# BPMLabLineSensor.net
KiCad netlist of a schematic drawn in EAGLE
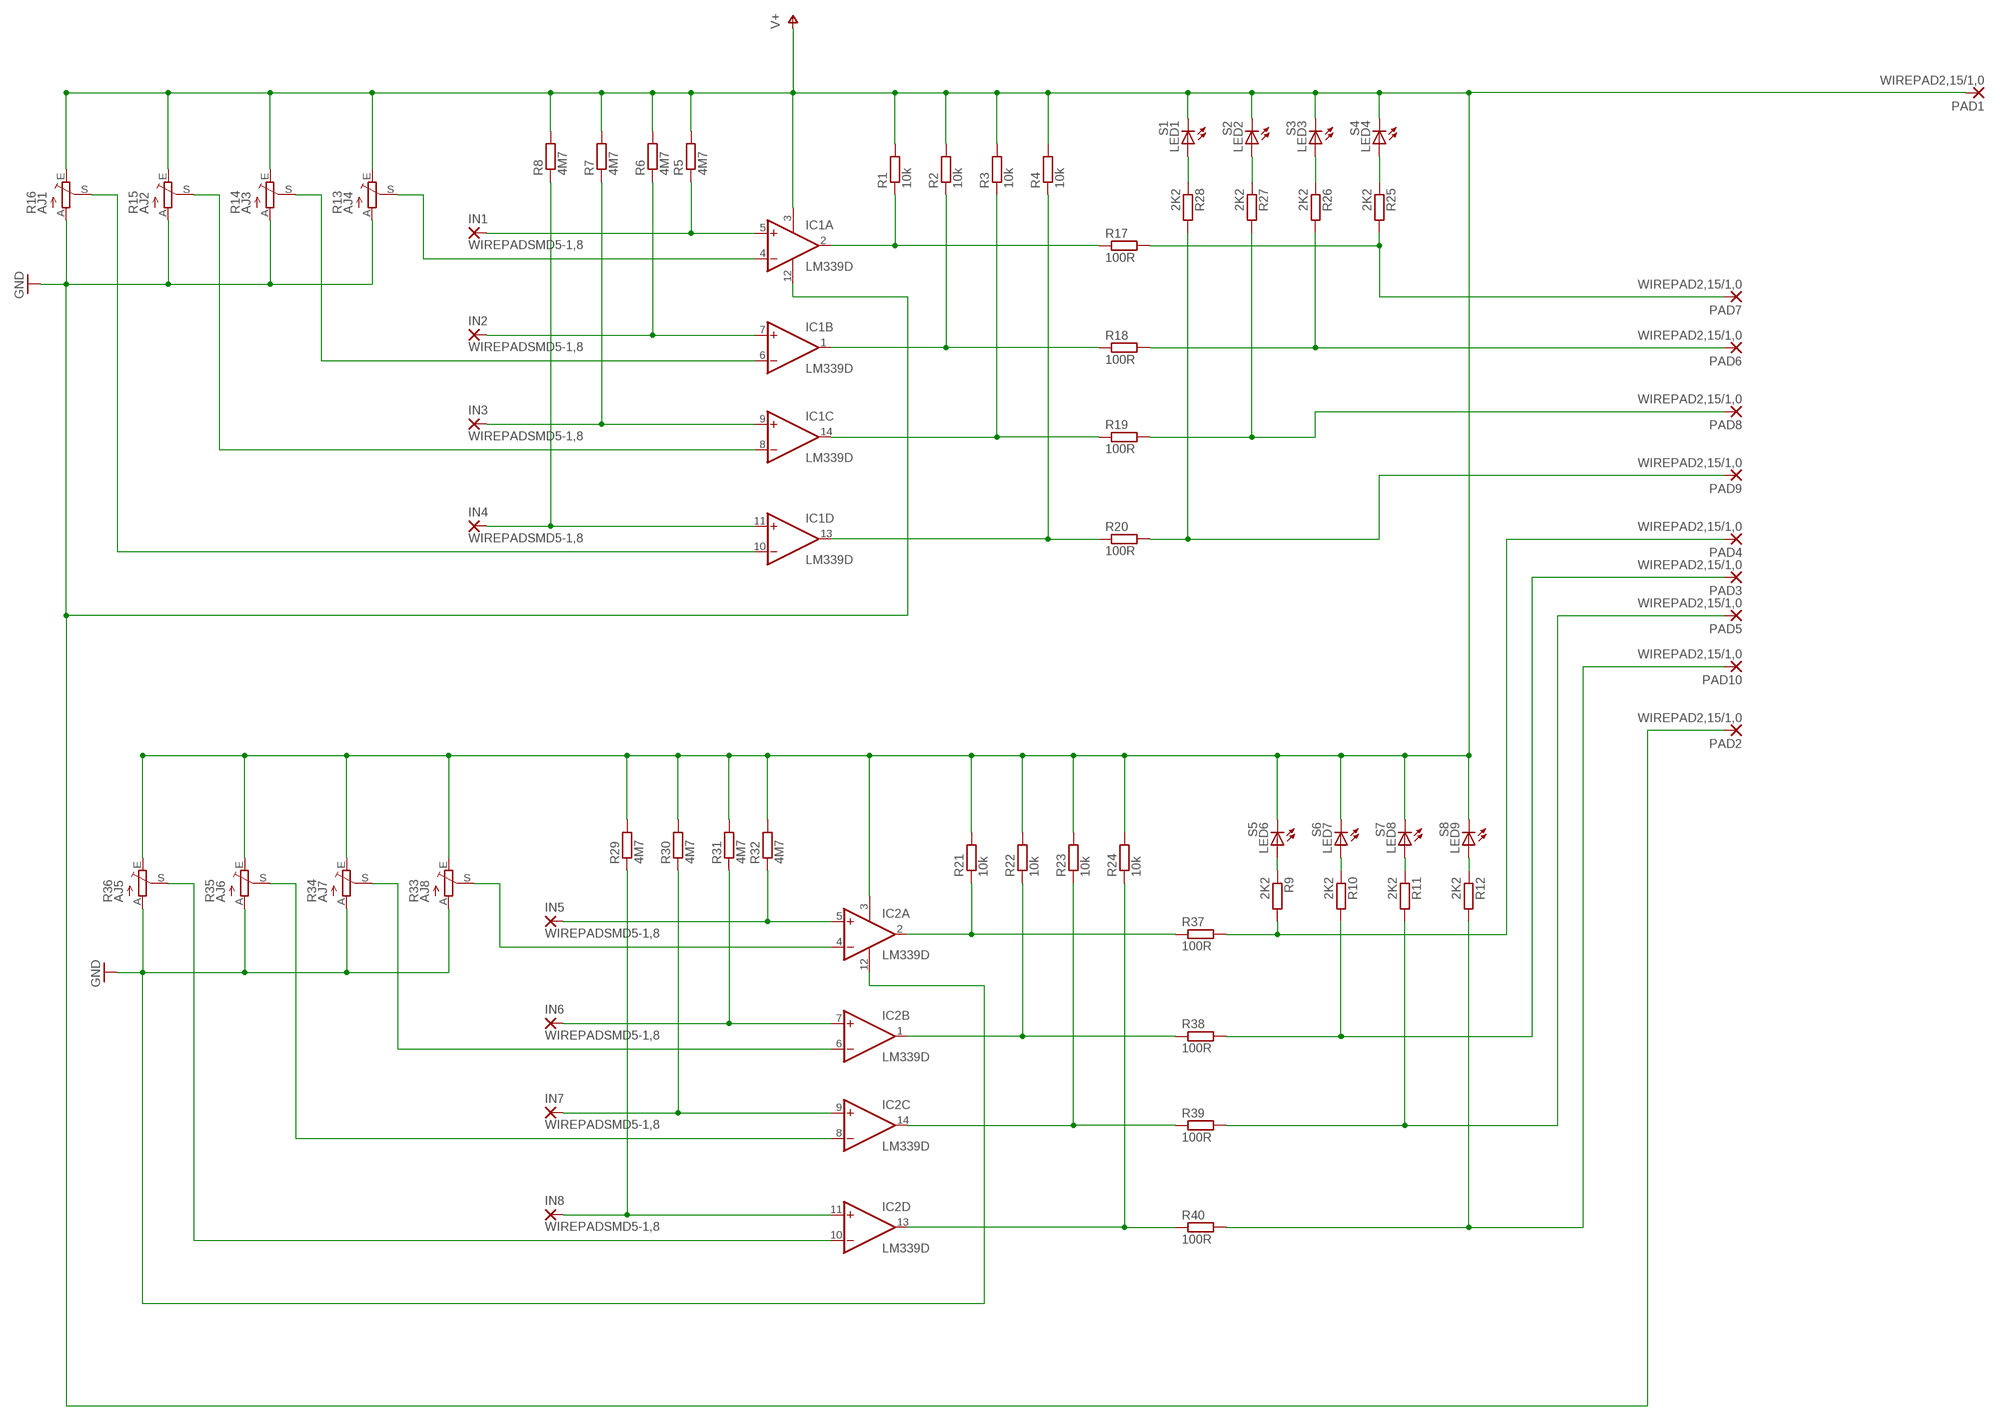
[diagram p0: schematic, sheet 1]

(export (version "E")
  (design (tool "Eeschema 10.0.6"))
  (components
    (comp (ref "IC1")
      (value "LM339D")
      (footprint "eagle-import:SO14")
      (libsource (lib "eagle-import") (part "LM339D"))
    )
    (comp (ref "IC2")
      (value "LM339D")
      (footprint "eagle-import:SO14")
      (libsource (lib "eagle-import") (part "LM339D"))
    )
    (comp (ref "IN1")
      (value "WIREPADSMD5-1,8")
      (footprint "eagle-import:5-1,8")
      (libsource (lib "eagle-import") (part "WIREPADSMD5-1,8"))
    )
    (comp (ref "IN2")
      (value "WIREPADSMD5-1,8")
      (footprint "eagle-import:5-1,8")
      (libsource (lib "eagle-import") (part "WIREPADSMD5-1,8"))
    )
    (comp (ref "IN3")
      (value "WIREPADSMD5-1,8")
      (footprint "eagle-import:5-1,8")
      (libsource (lib "eagle-import") (part "WIREPADSMD5-1,8"))
    )
    (comp (ref "IN4")
      (value "WIREPADSMD5-1,8")
      (footprint "eagle-import:5-1,8")
      (libsource (lib "eagle-import") (part "WIREPADSMD5-1,8"))
    )
    (comp (ref "IN5")
      (value "WIREPADSMD5-1,8")
      (footprint "eagle-import:5-1,8")
      (libsource (lib "eagle-import") (part "WIREPADSMD5-1,8"))
    )
    (comp (ref "IN6")
      (value "WIREPADSMD5-1,8")
      (footprint "eagle-import:5-1,8")
      (libsource (lib "eagle-import") (part "WIREPADSMD5-1,8"))
    )
    (comp (ref "IN7")
      (value "WIREPADSMD5-1,8")
      (footprint "eagle-import:5-1,8")
      (libsource (lib "eagle-import") (part "WIREPADSMD5-1,8"))
    )
    (comp (ref "IN8")
      (value "WIREPADSMD5-1,8")
      (footprint "eagle-import:5-1,8")
      (libsource (lib "eagle-import") (part "WIREPADSMD5-1,8"))
    )
    (comp (ref "LED1")
      (value "S1")
      (footprint "eagle-import:LED5MM")
      (libsource (lib "eagle-import") (part "LED5MM"))
    )
    (comp (ref "LED2")
      (value "S2")
      (footprint "eagle-import:LED5MM")
      (libsource (lib "eagle-import") (part "LED5MM"))
    )
    (comp (ref "LED3")
      (value "S3")
      (footprint "eagle-import:LED5MM")
      (libsource (lib "eagle-import") (part "LED5MM"))
    )
    (comp (ref "LED4")
      (value "S4")
      (footprint "eagle-import:LED5MM")
      (libsource (lib "eagle-import") (part "LED5MM"))
    )
    (comp (ref "LED6")
      (value "S5")
      (footprint "eagle-import:LED5MM")
      (libsource (lib "eagle-import") (part "LED5MM"))
    )
    (comp (ref "LED7")
      (value "S6")
      (footprint "eagle-import:LED5MM")
      (libsource (lib "eagle-import") (part "LED5MM"))
    )
    (comp (ref "LED8")
      (value "S7")
      (footprint "eagle-import:LED5MM")
      (libsource (lib "eagle-import") (part "LED5MM"))
    )
    (comp (ref "LED9")
      (value "S8")
      (footprint "eagle-import:LED5MM")
      (libsource (lib "eagle-import") (part "LED5MM"))
    )
    (comp (ref "PAD1")
      (value "WIREPAD2,15/1,0")
      (footprint "eagle-import:2,15_1,0")
      (libsource (lib "eagle-import") (part "WIREPAD2,15/1,0"))
    )
    (comp (ref "PAD2")
      (value "WIREPAD2,15/1,0")
      (footprint "eagle-import:2,15_1,0")
      (libsource (lib "eagle-import") (part "WIREPAD2,15/1,0"))
    )
    (comp (ref "PAD3")
      (value "WIREPAD2,15/1,0")
      (footprint "eagle-import:2,15_1,0")
      (libsource (lib "eagle-import") (part "WIREPAD2,15/1,0"))
    )
    (comp (ref "PAD4")
      (value "WIREPAD2,15/1,0")
      (footprint "eagle-import:2,15_1,0")
      (libsource (lib "eagle-import") (part "WIREPAD2,15/1,0"))
    )
    (comp (ref "PAD5")
      (value "WIREPAD2,15/1,0")
      (footprint "eagle-import:2,15_1,0")
      (libsource (lib "eagle-import") (part "WIREPAD2,15/1,0"))
    )
    (comp (ref "PAD6")
      (value "WIREPAD2,15/1,0")
      (footprint "eagle-import:2,15_1,0")
      (libsource (lib "eagle-import") (part "WIREPAD2,15/1,0"))
    )
    (comp (ref "PAD7")
      (value "WIREPAD2,15/1,0")
      (footprint "eagle-import:2,15_1,0")
      (libsource (lib "eagle-import") (part "WIREPAD2,15/1,0"))
    )
    (comp (ref "PAD8")
      (value "WIREPAD2,15/1,0")
      (footprint "eagle-import:2,15_1,0")
      (libsource (lib "eagle-import") (part "WIREPAD2,15/1,0"))
    )
    (comp (ref "PAD9")
      (value "WIREPAD2,15/1,0")
      (footprint "eagle-import:2,15_1,0")
      (libsource (lib "eagle-import") (part "WIREPAD2,15/1,0"))
    )
    (comp (ref "PAD10")
      (value "WIREPAD2,15/1,0")
      (footprint "eagle-import:2,15_1,0")
      (libsource (lib "eagle-import") (part "WIREPAD2,15/1,0"))
    )
    (comp (ref "R1")
      (value "10k")
      (footprint "eagle-import:M0805")
      (libsource (lib "eagle-import") (part "R-EU_M0805"))
    )
    (comp (ref "R2")
      (value "10k")
      (footprint "eagle-import:M0805")
      (libsource (lib "eagle-import") (part "R-EU_M0805"))
    )
    (comp (ref "R3")
      (value "10k")
      (footprint "eagle-import:M0805")
      (libsource (lib "eagle-import") (part "R-EU_M0805"))
    )
    (comp (ref "R4")
      (value "10k")
      (footprint "eagle-import:M0805")
      (libsource (lib "eagle-import") (part "R-EU_M0805"))
    )
    (comp (ref "R5")
      (value "4M7")
      (footprint "eagle-import:M0805")
      (libsource (lib "eagle-import") (part "R-EU_M0805"))
    )
    (comp (ref "R6")
      (value "4M7")
      (footprint "eagle-import:M0805")
      (libsource (lib "eagle-import") (part "R-EU_M0805"))
    )
    (comp (ref "R7")
      (value "4M7")
      (footprint "eagle-import:M0805")
      (libsource (lib "eagle-import") (part "R-EU_M0805"))
    )
    (comp (ref "R8")
      (value "4M7")
      (footprint "eagle-import:M0805")
      (libsource (lib "eagle-import") (part "R-EU_M0805"))
    )
    (comp (ref "R9")
      (value "2K2")
      (footprint "eagle-import:M0805")
      (libsource (lib "eagle-import") (part "R-EU_M0805"))
    )
    (comp (ref "R10")
      (value "2K2")
      (footprint "eagle-import:M0805")
      (libsource (lib "eagle-import") (part "R-EU_M0805"))
    )
    (comp (ref "R11")
      (value "2K2")
      (footprint "eagle-import:M0805")
      (libsource (lib "eagle-import") (part "R-EU_M0805"))
    )
    (comp (ref "R12")
      (value "2K2")
      (footprint "eagle-import:M0805")
      (libsource (lib "eagle-import") (part "R-EU_M0805"))
    )
    (comp (ref "R13")
      (value "AJ4")
      (footprint "eagle-import:RS3")
      (libsource (lib "eagle-import") (part "TRIM_EU-RS3"))
    )
    (comp (ref "R14")
      (value "AJ3")
      (footprint "eagle-import:RS3")
      (libsource (lib "eagle-import") (part "TRIM_EU-RS3"))
    )
    (comp (ref "R15")
      (value "AJ2")
      (footprint "eagle-import:RS3")
      (libsource (lib "eagle-import") (part "TRIM_EU-RS3"))
    )
    (comp (ref "R16")
      (value "AJ1")
      (footprint "eagle-import:RS3")
      (libsource (lib "eagle-import") (part "TRIM_EU-RS3"))
    )
    (comp (ref "R17")
      (value "100R")
      (footprint "eagle-import:0204_7")
      (libsource (lib "eagle-import") (part "R-EU_0204/7"))
    )
    (comp (ref "R18")
      (value "100R")
      (footprint "eagle-import:0204_7")
      (libsource (lib "eagle-import") (part "R-EU_0204/7"))
    )
    (comp (ref "R19")
      (value "100R")
      (footprint "eagle-import:0204_7")
      (libsource (lib "eagle-import") (part "R-EU_0204/7"))
    )
    (comp (ref "R20")
      (value "100R")
      (footprint "eagle-import:0204_7")
      (libsource (lib "eagle-import") (part "R-EU_0204/7"))
    )
    (comp (ref "R21")
      (value "10k")
      (footprint "eagle-import:M0805")
      (libsource (lib "eagle-import") (part "R-EU_M0805"))
    )
    (comp (ref "R22")
      (value "10k")
      (footprint "eagle-import:M0805")
      (libsource (lib "eagle-import") (part "R-EU_M0805"))
    )
    (comp (ref "R23")
      (value "10k")
      (footprint "eagle-import:M0805")
      (libsource (lib "eagle-import") (part "R-EU_M0805"))
    )
    (comp (ref "R24")
      (value "10k")
      (footprint "eagle-import:M0805")
      (libsource (lib "eagle-import") (part "R-EU_M0805"))
    )
    (comp (ref "R25")
      (value "2K2")
      (footprint "eagle-import:M0805")
      (libsource (lib "eagle-import") (part "R-EU_M0805"))
    )
    (comp (ref "R26")
      (value "2K2")
      (footprint "eagle-import:M0805")
      (libsource (lib "eagle-import") (part "R-EU_M0805"))
    )
    (comp (ref "R27")
      (value "2K2")
      (footprint "eagle-import:M0805")
      (libsource (lib "eagle-import") (part "R-EU_M0805"))
    )
    (comp (ref "R28")
      (value "2K2")
      (footprint "eagle-import:M0805")
      (libsource (lib "eagle-import") (part "R-EU_M0805"))
    )
    (comp (ref "R29")
      (value "4M7")
      (footprint "eagle-import:M0805")
      (libsource (lib "eagle-import") (part "R-EU_M0805"))
    )
    (comp (ref "R30")
      (value "4M7")
      (footprint "eagle-import:M0805")
      (libsource (lib "eagle-import") (part "R-EU_M0805"))
    )
    (comp (ref "R31")
      (value "4M7")
      (footprint "eagle-import:M0805")
      (libsource (lib "eagle-import") (part "R-EU_M0805"))
    )
    (comp (ref "R32")
      (value "4M7")
      (footprint "eagle-import:M0805")
      (libsource (lib "eagle-import") (part "R-EU_M0805"))
    )
    (comp (ref "R33")
      (value "AJ8")
      (footprint "eagle-import:RS3")
      (libsource (lib "eagle-import") (part "TRIM_EU-RS3"))
    )
    (comp (ref "R34")
      (value "AJ7")
      (footprint "eagle-import:RS3")
      (libsource (lib "eagle-import") (part "TRIM_EU-RS3"))
    )
    (comp (ref "R35")
      (value "AJ6")
      (footprint "eagle-import:RS3")
      (libsource (lib "eagle-import") (part "TRIM_EU-RS3"))
    )
    (comp (ref "R36")
      (value "AJ5")
      (footprint "eagle-import:RS3")
      (libsource (lib "eagle-import") (part "TRIM_EU-RS3"))
    )
    (comp (ref "R37")
      (value "100R")
      (footprint "eagle-import:0204_7")
      (libsource (lib "eagle-import") (part "R-EU_0204/7"))
    )
    (comp (ref "R38")
      (value "100R")
      (footprint "eagle-import:0204_7")
      (libsource (lib "eagle-import") (part "R-EU_0204/7"))
    )
    (comp (ref "R39")
      (value "100R")
      (footprint "eagle-import:0204_7")
      (libsource (lib "eagle-import") (part "R-EU_0204/7"))
    )
    (comp (ref "R40")
      (value "100R")
      (footprint "eagle-import:0204_7")
      (libsource (lib "eagle-import") (part "R-EU_0204/7"))
    )
  )
  (nets
    (net (code "1") (name "GND") (class "Default")
      (node (ref "IC1") (pin "12") (pinfunction "GND_12") (pintype "power_in"))
      (node (ref "IC2") (pin "12") (pinfunction "GND_12") (pintype "power_in"))
      (node (ref "PAD2") (pin "1") (pinfunction "P_1") (pintype "passive"))
      (node (ref "R13") (pin "A") (pinfunction "A_A") (pintype "passive"))
      (node (ref "R14") (pin "A") (pinfunction "A_A") (pintype "passive"))
      (node (ref "R15") (pin "A") (pinfunction "A_A") (pintype "passive"))
      (node (ref "R16") (pin "A") (pinfunction "A_A") (pintype "passive"))
      (node (ref "R33") (pin "A") (pinfunction "A_A") (pintype "passive"))
      (node (ref "R34") (pin "A") (pinfunction "A_A") (pintype "passive"))
      (node (ref "R35") (pin "A") (pinfunction "A_A") (pintype "passive"))
      (node (ref "R36") (pin "A") (pinfunction "A_A") (pintype "passive"))
    )
    (net (code "2") (name "Net-(IC1A-+IN)") (class "Default")
      (node (ref "IC1") (pin "5") (pinfunction "+IN_5") (pintype "input"))
      (node (ref "IN1") (pin "1") (pinfunction "P_1") (pintype "passive"))
      (node (ref "R5") (pin "1") (pinfunction "1_1") (pintype "passive"))
    )
    (net (code "3") (name "Net-(IC1A--IN)") (class "Default")
      (node (ref "IC1") (pin "4") (pinfunction "-IN_4") (pintype "input"))
      (node (ref "R13") (pin "S") (pinfunction "S_S") (pintype "passive"))
    )
    (net (code "4") (name "Net-(IC1A-OUT)") (class "Default")
      (node (ref "IC1") (pin "2") (pinfunction "OUT_2") (pintype "open_collector"))
      (node (ref "R1") (pin "1") (pinfunction "1_1") (pintype "passive"))
      (node (ref "R17") (pin "1") (pinfunction "1_1") (pintype "passive"))
    )
    (net (code "5") (name "Net-(IC1B-+IN)") (class "Default")
      (node (ref "IC1") (pin "7") (pinfunction "+IN_7") (pintype "input"))
      (node (ref "IN2") (pin "1") (pinfunction "P_1") (pintype "passive"))
      (node (ref "R6") (pin "1") (pinfunction "1_1") (pintype "passive"))
    )
    (net (code "6") (name "Net-(IC1B--IN)") (class "Default")
      (node (ref "IC1") (pin "6") (pinfunction "-IN_6") (pintype "input"))
      (node (ref "R14") (pin "S") (pinfunction "S_S") (pintype "passive"))
    )
    (net (code "7") (name "Net-(IC1B-OUT)") (class "Default")
      (node (ref "IC1") (pin "1") (pinfunction "OUT_1") (pintype "open_collector"))
      (node (ref "R18") (pin "1") (pinfunction "1_1") (pintype "passive"))
      (node (ref "R2") (pin "1") (pinfunction "1_1") (pintype "passive"))
    )
    (net (code "8") (name "Net-(IC1C-+IN)") (class "Default")
      (node (ref "IC1") (pin "9") (pinfunction "+IN_9") (pintype "input"))
      (node (ref "IN3") (pin "1") (pinfunction "P_1") (pintype "passive"))
      (node (ref "R7") (pin "1") (pinfunction "1_1") (pintype "passive"))
    )
    (net (code "9") (name "Net-(IC1C--IN)") (class "Default")
      (node (ref "IC1") (pin "8") (pinfunction "-IN_8") (pintype "input"))
      (node (ref "R15") (pin "S") (pinfunction "S_S") (pintype "passive"))
    )
    (net (code "10") (name "Net-(IC1C-OUT)") (class "Default")
      (node (ref "IC1") (pin "14") (pinfunction "OUT_14") (pintype "open_collector"))
      (node (ref "R19") (pin "1") (pinfunction "1_1") (pintype "passive"))
      (node (ref "R3") (pin "1") (pinfunction "1_1") (pintype "passive"))
    )
    (net (code "11") (name "Net-(IC1D-+IN)") (class "Default")
      (node (ref "IC1") (pin "11") (pinfunction "+IN_11") (pintype "input"))
      (node (ref "IN4") (pin "1") (pinfunction "P_1") (pintype "passive"))
      (node (ref "R8") (pin "1") (pinfunction "1_1") (pintype "passive"))
    )
    (net (code "12") (name "Net-(IC1D--IN)") (class "Default")
      (node (ref "IC1") (pin "10") (pinfunction "-IN_10") (pintype "input"))
      (node (ref "R16") (pin "S") (pinfunction "S_S") (pintype "passive"))
    )
    (net (code "13") (name "Net-(IC1D-OUT)") (class "Default")
      (node (ref "IC1") (pin "13") (pinfunction "OUT_13") (pintype "open_collector"))
      (node (ref "R20") (pin "1") (pinfunction "1_1") (pintype "passive"))
      (node (ref "R4") (pin "1") (pinfunction "1_1") (pintype "passive"))
    )
    (net (code "14") (name "Net-(IC2A-+IN)") (class "Default")
      (node (ref "IC2") (pin "5") (pinfunction "+IN_5") (pintype "input"))
      (node (ref "IN5") (pin "1") (pinfunction "P_1") (pintype "passive"))
      (node (ref "R32") (pin "1") (pinfunction "1_1") (pintype "passive"))
    )
    (net (code "15") (name "Net-(IC2A--IN)") (class "Default")
      (node (ref "IC2") (pin "4") (pinfunction "-IN_4") (pintype "input"))
      (node (ref "R33") (pin "S") (pinfunction "S_S") (pintype "passive"))
    )
    (net (code "16") (name "Net-(IC2A-OUT)") (class "Default")
      (node (ref "IC2") (pin "2") (pinfunction "OUT_2") (pintype "open_collector"))
      (node (ref "R21") (pin "1") (pinfunction "1_1") (pintype "passive"))
      (node (ref "R37") (pin "1") (pinfunction "1_1") (pintype "passive"))
    )
    (net (code "17") (name "Net-(IC2B-+IN)") (class "Default")
      (node (ref "IC2") (pin "7") (pinfunction "+IN_7") (pintype "input"))
      (node (ref "IN6") (pin "1") (pinfunction "P_1") (pintype "passive"))
      (node (ref "R31") (pin "1") (pinfunction "1_1") (pintype "passive"))
    )
    (net (code "18") (name "Net-(IC2B--IN)") (class "Default")
      (node (ref "IC2") (pin "6") (pinfunction "-IN_6") (pintype "input"))
      (node (ref "R34") (pin "S") (pinfunction "S_S") (pintype "passive"))
    )
    (net (code "19") (name "Net-(IC2B-OUT)") (class "Default")
      (node (ref "IC2") (pin "1") (pinfunction "OUT_1") (pintype "open_collector"))
      (node (ref "R22") (pin "1") (pinfunction "1_1") (pintype "passive"))
      (node (ref "R38") (pin "1") (pinfunction "1_1") (pintype "passive"))
    )
    (net (code "20") (name "Net-(IC2C-+IN)") (class "Default")
      (node (ref "IC2") (pin "9") (pinfunction "+IN_9") (pintype "input"))
      (node (ref "IN7") (pin "1") (pinfunction "P_1") (pintype "passive"))
      (node (ref "R30") (pin "1") (pinfunction "1_1") (pintype "passive"))
    )
    (net (code "21") (name "Net-(IC2C--IN)") (class "Default")
      (node (ref "IC2") (pin "8") (pinfunction "-IN_8") (pintype "input"))
      (node (ref "R35") (pin "S") (pinfunction "S_S") (pintype "passive"))
    )
    (net (code "22") (name "Net-(IC2C-OUT)") (class "Default")
      (node (ref "IC2") (pin "14") (pinfunction "OUT_14") (pintype "open_collector"))
      (node (ref "R23") (pin "1") (pinfunction "1_1") (pintype "passive"))
      (node (ref "R39") (pin "1") (pinfunction "1_1") (pintype "passive"))
    )
    (net (code "23") (name "Net-(IC2D-+IN)") (class "Default")
      (node (ref "IC2") (pin "11") (pinfunction "+IN_11") (pintype "input"))
      (node (ref "IN8") (pin "1") (pinfunction "P_1") (pintype "passive"))
      (node (ref "R29") (pin "1") (pinfunction "1_1") (pintype "passive"))
    )
    (net (code "24") (name "Net-(IC2D--IN)") (class "Default")
      (node (ref "IC2") (pin "10") (pinfunction "-IN_10") (pintype "input"))
      (node (ref "R36") (pin "S") (pinfunction "S_S") (pintype "passive"))
    )
    (net (code "25") (name "Net-(IC2D-OUT)") (class "Default")
      (node (ref "IC2") (pin "13") (pinfunction "OUT_13") (pintype "open_collector"))
      (node (ref "R24") (pin "1") (pinfunction "1_1") (pintype "passive"))
      (node (ref "R40") (pin "1") (pinfunction "1_1") (pintype "passive"))
    )
    (net (code "26") (name "Net-(LED1-PadA)") (class "Default")
      (node (ref "LED1") (pin "A") (pinfunction "A_A") (pintype "passive"))
      (node (ref "R28") (pin "1") (pinfunction "1_1") (pintype "passive"))
    )
    (net (code "27") (name "Net-(LED2-PadA)") (class "Default")
      (node (ref "LED2") (pin "A") (pinfunction "A_A") (pintype "passive"))
      (node (ref "R27") (pin "1") (pinfunction "1_1") (pintype "passive"))
    )
    (net (code "28") (name "Net-(LED3-PadA)") (class "Default")
      (node (ref "LED3") (pin "A") (pinfunction "A_A") (pintype "passive"))
      (node (ref "R26") (pin "1") (pinfunction "1_1") (pintype "passive"))
    )
    (net (code "29") (name "Net-(LED4-PadA)") (class "Default")
      (node (ref "LED4") (pin "A") (pinfunction "A_A") (pintype "passive"))
      (node (ref "R25") (pin "1") (pinfunction "1_1") (pintype "passive"))
    )
    (net (code "30") (name "Net-(LED6-PadA)") (class "Default")
      (node (ref "LED6") (pin "A") (pinfunction "A_A") (pintype "passive"))
      (node (ref "R9") (pin "1") (pinfunction "1_1") (pintype "passive"))
    )
    (net (code "31") (name "Net-(LED7-PadA)") (class "Default")
      (node (ref "LED7") (pin "A") (pinfunction "A_A") (pintype "passive"))
      (node (ref "R10") (pin "1") (pinfunction "1_1") (pintype "passive"))
    )
    (net (code "32") (name "Net-(LED8-PadA)") (class "Default")
      (node (ref "LED8") (pin "A") (pinfunction "A_A") (pintype "passive"))
      (node (ref "R11") (pin "1") (pinfunction "1_1") (pintype "passive"))
    )
    (net (code "33") (name "Net-(LED9-PadA)") (class "Default")
      (node (ref "LED9") (pin "A") (pinfunction "A_A") (pintype "passive"))
      (node (ref "R12") (pin "1") (pinfunction "1_1") (pintype "passive"))
    )
    (net (code "34") (name "Net-(PAD3-P)") (class "Default")
      (node (ref "PAD3") (pin "1") (pinfunction "P_1") (pintype "passive"))
      (node (ref "R10") (pin "2") (pinfunction "2_2") (pintype "passive"))
      (node (ref "R38") (pin "2") (pinfunction "2_2") (pintype "passive"))
    )
    (net (code "35") (name "Net-(PAD4-P)") (class "Default")
      (node (ref "PAD4") (pin "1") (pinfunction "P_1") (pintype "passive"))
      (node (ref "R37") (pin "2") (pinfunction "2_2") (pintype "passive"))
      (node (ref "R9") (pin "2") (pinfunction "2_2") (pintype "passive"))
    )
    (net (code "36") (name "Net-(PAD5-P)") (class "Default")
      (node (ref "PAD5") (pin "1") (pinfunction "P_1") (pintype "passive"))
      (node (ref "R11") (pin "2") (pinfunction "2_2") (pintype "passive"))
      (node (ref "R39") (pin "2") (pinfunction "2_2") (pintype "passive"))
    )
    (net (code "37") (name "Net-(PAD6-P)") (class "Default")
      (node (ref "PAD6") (pin "1") (pinfunction "P_1") (pintype "passive"))
      (node (ref "R18") (pin "2") (pinfunction "2_2") (pintype "passive"))
      (node (ref "R26") (pin "2") (pinfunction "2_2") (pintype "passive"))
    )
    (net (code "38") (name "Net-(PAD7-P)") (class "Default")
      (node (ref "PAD7") (pin "1") (pinfunction "P_1") (pintype "passive"))
      (node (ref "R17") (pin "2") (pinfunction "2_2") (pintype "passive"))
      (node (ref "R25") (pin "2") (pinfunction "2_2") (pintype "passive"))
    )
    (net (code "39") (name "Net-(PAD8-P)") (class "Default")
      (node (ref "PAD8") (pin "1") (pinfunction "P_1") (pintype "passive"))
      (node (ref "R19") (pin "2") (pinfunction "2_2") (pintype "passive"))
      (node (ref "R27") (pin "2") (pinfunction "2_2") (pintype "passive"))
    )
    (net (code "40") (name "Net-(PAD9-P)") (class "Default")
      (node (ref "PAD9") (pin "1") (pinfunction "P_1") (pintype "passive"))
      (node (ref "R20") (pin "2") (pinfunction "2_2") (pintype "passive"))
      (node (ref "R28") (pin "2") (pinfunction "2_2") (pintype "passive"))
    )
    (net (code "41") (name "Net-(PAD10-P)") (class "Default")
      (node (ref "PAD10") (pin "1") (pinfunction "P_1") (pintype "passive"))
      (node (ref "R12") (pin "2") (pinfunction "2_2") (pintype "passive"))
      (node (ref "R40") (pin "2") (pinfunction "2_2") (pintype "passive"))
    )
    (net (code "42") (name "V+") (class "Default")
      (node (ref "IC1") (pin "3") (pinfunction "V+_3") (pintype "power_in"))
      (node (ref "IC2") (pin "3") (pinfunction "V+_3") (pintype "power_in"))
      (node (ref "LED1") (pin "K") (pinfunction "C_K") (pintype "passive"))
      (node (ref "LED2") (pin "K") (pinfunction "C_K") (pintype "passive"))
      (node (ref "LED3") (pin "K") (pinfunction "C_K") (pintype "passive"))
      (node (ref "LED4") (pin "K") (pinfunction "C_K") (pintype "passive"))
      (node (ref "LED6") (pin "K") (pinfunction "C_K") (pintype "passive"))
      (node (ref "LED7") (pin "K") (pinfunction "C_K") (pintype "passive"))
      (node (ref "LED8") (pin "K") (pinfunction "C_K") (pintype "passive"))
      (node (ref "LED9") (pin "K") (pinfunction "C_K") (pintype "passive"))
      (node (ref "PAD1") (pin "1") (pinfunction "P_1") (pintype "passive"))
      (node (ref "R1") (pin "2") (pinfunction "2_2") (pintype "passive"))
      (node (ref "R13") (pin "E") (pinfunction "E_E") (pintype "passive"))
      (node (ref "R14") (pin "E") (pinfunction "E_E") (pintype "passive"))
      (node (ref "R15") (pin "E") (pinfunction "E_E") (pintype "passive"))
      (node (ref "R16") (pin "E") (pinfunction "E_E") (pintype "passive"))
      (node (ref "R2") (pin "2") (pinfunction "2_2") (pintype "passive"))
      (node (ref "R21") (pin "2") (pinfunction "2_2") (pintype "passive"))
      (node (ref "R22") (pin "2") (pinfunction "2_2") (pintype "passive"))
      (node (ref "R23") (pin "2") (pinfunction "2_2") (pintype "passive"))
      (node (ref "R24") (pin "2") (pinfunction "2_2") (pintype "passive"))
      (node (ref "R29") (pin "2") (pinfunction "2_2") (pintype "passive"))
      (node (ref "R3") (pin "2") (pinfunction "2_2") (pintype "passive"))
      (node (ref "R30") (pin "2") (pinfunction "2_2") (pintype "passive"))
      (node (ref "R31") (pin "2") (pinfunction "2_2") (pintype "passive"))
      (node (ref "R32") (pin "2") (pinfunction "2_2") (pintype "passive"))
      (node (ref "R33") (pin "E") (pinfunction "E_E") (pintype "passive"))
      (node (ref "R34") (pin "E") (pinfunction "E_E") (pintype "passive"))
      (node (ref "R35") (pin "E") (pinfunction "E_E") (pintype "passive"))
      (node (ref "R36") (pin "E") (pinfunction "E_E") (pintype "passive"))
      (node (ref "R4") (pin "2") (pinfunction "2_2") (pintype "passive"))
      (node (ref "R5") (pin "2") (pinfunction "2_2") (pintype "passive"))
      (node (ref "R6") (pin "2") (pinfunction "2_2") (pintype "passive"))
      (node (ref "R7") (pin "2") (pinfunction "2_2") (pintype "passive"))
      (node (ref "R8") (pin "2") (pinfunction "2_2") (pintype "passive"))
    )
  )
)
